# PIC_Schematic.net
KiCad netlist of a schematic drawn in Altium Designer
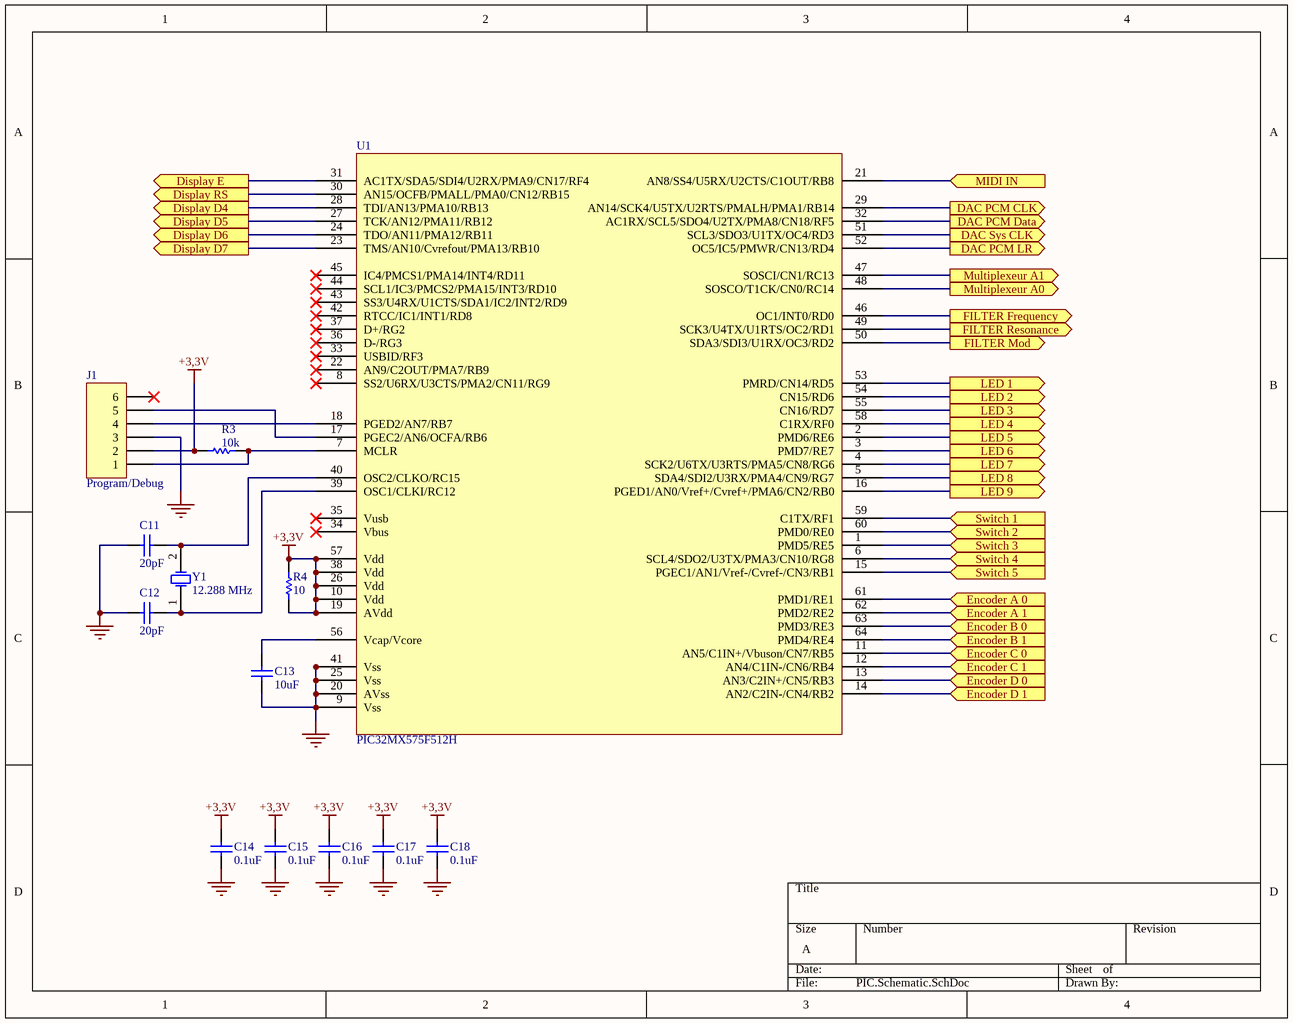
[diagram p0: PIC.Schematic.SchDoc]

(export (version "E")
  (design (tool "Eeschema 10.0.6"))
  (components
    (comp (ref "C11")
      (value "20pF")
      (footprint "CAPC1608N")
      (description "Capacitor (Semiconductor SIM Model)")
      (fields (field (name "PUBLISHER") "Altium Limited"))
      (libsource (lib "Miscellaneous Devices") (part "Cap Semi"))
    )
    (comp (ref "C12")
      (value "20pF")
      (footprint "CAPC1608N")
      (description "Capacitor (Semiconductor SIM Model)")
      (fields (field (name "PUBLISHER") "Altium Limited"))
      (libsource (lib "Miscellaneous Devices") (part "Cap Semi"))
    )
    (comp (ref "C13")
      (value "10uF")
      (footprint "CAPC1608N")
      (description "Capacitor")
      (fields (field (name "PUBLISHER") "Altium Limited"))
      (libsource (lib "Miscellaneous Devices") (part "Cap"))
    )
    (comp (ref "C14")
      (value "0.1uF")
      (footprint "CAPC1608N")
      (description "Capacitor (Semiconductor SIM Model)")
      (fields (field (name "PUBLISHER") "Altium Limited"))
      (libsource (lib "Miscellaneous Devices") (part "Cap Semi"))
    )
    (comp (ref "C15")
      (value "0.1uF")
      (footprint "CAPC1608N")
      (description "Capacitor (Semiconductor SIM Model)")
      (fields (field (name "PUBLISHER") "Altium Limited"))
      (libsource (lib "Miscellaneous Devices") (part "Cap Semi"))
    )
    (comp (ref "C16")
      (value "0.1uF")
      (footprint "CAPC1608N")
      (description "Capacitor (Semiconductor SIM Model)")
      (fields (field (name "PUBLISHER") "Altium Limited"))
      (libsource (lib "Miscellaneous Devices") (part "Cap Semi"))
    )
    (comp (ref "C17")
      (value "0.1uF")
      (footprint "CAPC1608N")
      (description "Capacitor (Semiconductor SIM Model)")
      (fields (field (name "PUBLISHER") "Altium Limited"))
      (libsource (lib "Miscellaneous Devices") (part "Cap Semi"))
    )
    (comp (ref "C18")
      (value "0.1uF")
      (footprint "CAPC1608N")
      (description "Capacitor (Semiconductor SIM Model)")
      (fields (field (name "PUBLISHER") "Altium Limited"))
      (libsource (lib "Miscellaneous Devices") (part "Cap Semi"))
    )
    (comp (ref "J1")
      (value "Program/Debug")
      (footprint "RJ11")
      (description "Header, 6-Pin, Right Angle")
      (fields (field (name "PUBLISHER") "Altium Limited"))
      (libsource (lib "Miscellaneous Connectors") (part "Header 6H"))
    )
    (comp (ref "R3")
      (value "10k")
      (footprint "CAPC1608N")
      (description "Resistor")
      (fields (field (name "PUBLISHER") "Altium Limited"))
      (libsource (lib "Miscellaneous Devices") (part "Res1"))
    )
    (comp (ref "R4")
      (value "10")
      (footprint "CAPC1608N")
      (description "Resistor")
      (fields (field (name "PUBLISHER") "Altium Limited"))
      (libsource (lib "Miscellaneous Devices") (part "Res1"))
    )
    (comp (ref "U1")
      (value "PIC32MX575F512H")
      (footprint "PIC32")
      (libsource (lib "SynthyTwo.Components") (part "PIC32 MX575F512H"))
    )
    (comp (ref "Y1")
      (value "12.288 MHz")
      (footprint "Xtal")
      (description "Crystal Oscillator")
      (fields (field (name "PUBLISHER") "Altium Limited"))
      (libsource (lib "Miscellaneous Devices") (part "XTAL"))
    )
  )
  (nets
    (net (code "1") (name "+3,3V") (class "Default")
      (node (ref "C14") (pin "2") (pinfunction "2_2") (pintype "passive"))
      (node (ref "C15") (pin "2") (pinfunction "2_2") (pintype "passive"))
      (node (ref "C16") (pin "2") (pinfunction "2_2") (pintype "passive"))
      (node (ref "C17") (pin "2") (pinfunction "2_2") (pintype "passive"))
      (node (ref "C18") (pin "2") (pinfunction "2_2") (pintype "passive"))
      (node (ref "J1") (pin "2") (pinfunction "2_2") (pintype "passive"))
      (node (ref "R3") (pin "2") (pinfunction "2_2") (pintype "passive"))
      (node (ref "R4") (pin "1") (pinfunction "1_1") (pintype "passive"))
      (node (ref "R4") (pin "2") (pinfunction "2_2") (pintype "passive"))
      (node (ref "U1") (pin "10") (pinfunction "Vdd_10") (pintype "passive"))
      (node (ref "U1") (pin "19") (pinfunction "AVdd_19") (pintype "passive"))
      (node (ref "U1") (pin "26") (pinfunction "Vdd_26") (pintype "passive"))
      (node (ref "U1") (pin "38") (pinfunction "Vdd_38") (pintype "passive"))
      (node (ref "U1") (pin "57") (pinfunction "Vdd_57") (pintype "passive"))
    )
    (net (code "2") (name "/DAC PCM CLK") (class "Default")
      (node (ref "U1") (pin "29") (pinfunction "AN14/SCK4/U5TX/U2RTS/PMALH/PMA1/RB14_29") (pintype "passive"))
    )
    (net (code "3") (name "/DAC PCM Data") (class "Default")
      (node (ref "U1") (pin "32") (pinfunction "AC1RX/SCL5/SDO4/U2TX/PMA8/CN18/RF5_32") (pintype "passive"))
    )
    (net (code "4") (name "/DAC PCM LR") (class "Default")
      (node (ref "U1") (pin "52") (pinfunction "OC5/IC5/PMWR/CN13/RD4_52") (pintype "passive"))
    )
    (net (code "5") (name "/DAC Sys CLK") (class "Default")
      (node (ref "U1") (pin "51") (pinfunction "SCL3/SDO3/U1TX/OC4/RD3_51") (pintype "passive"))
    )
    (net (code "6") (name "/Display D4") (class "Default")
      (node (ref "U1") (pin "28") (pinfunction "TDI/AN13/PMA10/RB13_28") (pintype "passive"))
    )
    (net (code "7") (name "/Display D5") (class "Default")
      (node (ref "U1") (pin "27") (pinfunction "TCK/AN12/PMA11/RB12_27") (pintype "passive"))
    )
    (net (code "8") (name "/Display D6") (class "Default")
      (node (ref "U1") (pin "24") (pinfunction "TDO/AN11/PMA12/RB11_24") (pintype "passive"))
    )
    (net (code "9") (name "/Display D7") (class "Default")
      (node (ref "U1") (pin "23") (pinfunction "TMS/AN10/Cvrefout/PMA13/RB10_23") (pintype "passive"))
    )
    (net (code "10") (name "/Display E") (class "Default")
      (node (ref "U1") (pin "31") (pinfunction "AC1TX/SDA5/SDI4/U2RX/PMA9/CN17/RF4_31") (pintype "passive"))
    )
    (net (code "11") (name "/Display RS") (class "Default")
      (node (ref "U1") (pin "30") (pinfunction "AN15/OCFB/PMALL/PMA0/CN12/RB15_30") (pintype "passive"))
    )
    (net (code "12") (name "/Encoder A 0") (class "Default")
      (node (ref "U1") (pin "61") (pinfunction "PMD1/RE1_61") (pintype "passive"))
    )
    (net (code "13") (name "/Encoder A 1") (class "Default")
      (node (ref "U1") (pin "62") (pinfunction "PMD2/RE2_62") (pintype "passive"))
    )
    (net (code "14") (name "/Encoder B 0") (class "Default")
      (node (ref "U1") (pin "63") (pinfunction "PMD3/RE3_63") (pintype "passive"))
    )
    (net (code "15") (name "/Encoder B 1") (class "Default")
      (node (ref "U1") (pin "64") (pinfunction "PMD4/RE4_64") (pintype "passive"))
    )
    (net (code "16") (name "/Encoder C 0") (class "Default")
      (node (ref "U1") (pin "11") (pinfunction "AN5/C1IN+/Vbuson/CN7/RB5_11") (pintype "passive"))
    )
    (net (code "17") (name "/Encoder C 1") (class "Default")
      (node (ref "U1") (pin "12") (pinfunction "AN4/C1IN-/CN6/RB4_12") (pintype "passive"))
    )
    (net (code "18") (name "/Encoder D 0") (class "Default")
      (node (ref "U1") (pin "13") (pinfunction "AN3/C2IN+/CN5/RB3_13") (pintype "passive"))
    )
    (net (code "19") (name "/Encoder D 1") (class "Default")
      (node (ref "U1") (pin "14") (pinfunction "AN2/C2IN-/CN4/RB2_14") (pintype "passive"))
    )
    (net (code "20") (name "/FILTER Frequency") (class "Default")
      (node (ref "U1") (pin "46") (pinfunction "OC1/INT0/RD0_46") (pintype "passive"))
    )
    (net (code "21") (name "/FILTER Mod") (class "Default")
      (node (ref "U1") (pin "50") (pinfunction "SDA3/SDI3/U1RX/OC3/RD2_50") (pintype "passive"))
    )
    (net (code "22") (name "/FILTER Resonance") (class "Default")
      (node (ref "U1") (pin "49") (pinfunction "SCK3/U4TX/U1RTS/OC2/RD1_49") (pintype "passive"))
    )
    (net (code "23") (name "/LED 1") (class "Default")
      (node (ref "U1") (pin "53") (pinfunction "PMRD/CN14/RD5_53") (pintype "passive"))
    )
    (net (code "24") (name "/LED 2") (class "Default")
      (node (ref "U1") (pin "54") (pinfunction "CN15/RD6_54") (pintype "passive"))
    )
    (net (code "25") (name "/LED 3") (class "Default")
      (node (ref "U1") (pin "55") (pinfunction "CN16/RD7_55") (pintype "passive"))
    )
    (net (code "26") (name "/LED 4") (class "Default")
      (node (ref "U1") (pin "58") (pinfunction "C1RX/RF0_58") (pintype "passive"))
    )
    (net (code "27") (name "/LED 5") (class "Default")
      (node (ref "U1") (pin "2") (pinfunction "PMD6/RE6_2") (pintype "passive"))
    )
    (net (code "28") (name "/LED 6") (class "Default")
      (node (ref "U1") (pin "3") (pinfunction "PMD7/RE7_3") (pintype "passive"))
    )
    (net (code "29") (name "/LED 7") (class "Default")
      (node (ref "U1") (pin "4") (pinfunction "SCK2/U6TX/U3RTS/PMA5/CN8/RG6_4") (pintype "passive"))
    )
    (net (code "30") (name "/LED 8") (class "Default")
      (node (ref "U1") (pin "5") (pinfunction "SDA4/SDI2/U3RX/PMA4/CN9/RG7_5") (pintype "passive"))
    )
    (net (code "31") (name "/LED 9") (class "Default")
      (node (ref "U1") (pin "16") (pinfunction "PGED1/AN0/Vref+/Cvref+/PMA6/CN2/RB0_16") (pintype "passive"))
    )
    (net (code "32") (name "/MIDI IN") (class "Default")
      (node (ref "U1") (pin "21") (pinfunction "AN8/SS4/U5RX/U2CTS/C1OUT/RB8_21") (pintype "passive"))
    )
    (net (code "33") (name "/Multiplexeur A0") (class "Default")
      (node (ref "U1") (pin "48") (pinfunction "SOSCO/T1CK/CN0/RC14_48") (pintype "passive"))
    )
    (net (code "34") (name "/Multiplexeur A1") (class "Default")
      (node (ref "U1") (pin "47") (pinfunction "SOSCI/CN1/RC13_47") (pintype "passive"))
    )
    (net (code "35") (name "/Switch 1") (class "Default")
      (node (ref "U1") (pin "59") (pinfunction "C1TX/RF1_59") (pintype "passive"))
    )
    (net (code "36") (name "/Switch 2") (class "Default")
      (node (ref "U1") (pin "60") (pinfunction "PMD0/RE0_60") (pintype "passive"))
    )
    (net (code "37") (name "/Switch 3") (class "Default")
      (node (ref "U1") (pin "1") (pinfunction "PMD5/RE5_1") (pintype "passive"))
    )
    (net (code "38") (name "/Switch 4") (class "Default")
      (node (ref "U1") (pin "6") (pinfunction "SCL4/SDO2/U3TX/PMA3/CN10/RG8_6") (pintype "passive"))
    )
    (net (code "39") (name "/Switch 5") (class "Default")
      (node (ref "U1") (pin "15") (pinfunction "PGEC1/AN1/Vref-/Cvref-/CN3/RB1_15") (pintype "passive"))
    )
    (net (code "40") (name "GND") (class "Default")
      (node (ref "C11") (pin "1") (pinfunction "1_1") (pintype "passive"))
      (node (ref "C12") (pin "1") (pinfunction "1_1") (pintype "passive"))
      (node (ref "C13") (pin "1") (pinfunction "1_1") (pintype "passive"))
      (node (ref "C14") (pin "1") (pinfunction "1_1") (pintype "passive"))
      (node (ref "C15") (pin "1") (pinfunction "1_1") (pintype "passive"))
      (node (ref "C16") (pin "1") (pinfunction "1_1") (pintype "passive"))
      (node (ref "C17") (pin "1") (pinfunction "1_1") (pintype "passive"))
      (node (ref "C18") (pin "1") (pinfunction "1_1") (pintype "passive"))
      (node (ref "J1") (pin "3") (pinfunction "3_3") (pintype "passive"))
      (node (ref "U1") (pin "20") (pinfunction "AVss_20") (pintype "passive"))
      (node (ref "U1") (pin "25") (pinfunction "Vss_25") (pintype "passive"))
      (node (ref "U1") (pin "41") (pinfunction "Vss_41") (pintype "passive"))
      (node (ref "U1") (pin "9") (pinfunction "Vss_9") (pintype "passive"))
    )
    (net (code "41") (name "Net-(U1-MCLR)") (class "Default")
      (node (ref "J1") (pin "1") (pinfunction "1_1") (pintype "passive"))
      (node (ref "R3") (pin "1") (pinfunction "1_1") (pintype "passive"))
      (node (ref "U1") (pin "7") (pinfunction "MCLR_7") (pintype "passive"))
    )
    (net (code "42") (name "Net-(U1-OSC1{slash}CLKI{slash}RC12)") (class "Default")
      (node (ref "C12") (pin "2") (pinfunction "2_2") (pintype "passive"))
      (node (ref "U1") (pin "39") (pinfunction "OSC1/CLKI/RC12_39") (pintype "passive"))
      (node (ref "Y1") (pin "1") (pinfunction "OSC1_1") (pintype "passive"))
    )
    (net (code "43") (name "Net-(U1-OSC2{slash}CLKO{slash}RC15)") (class "Default")
      (node (ref "C11") (pin "2") (pinfunction "2_2") (pintype "passive"))
      (node (ref "U1") (pin "40") (pinfunction "OSC2/CLKO/RC15_40") (pintype "passive"))
      (node (ref "Y1") (pin "2") (pinfunction "OSC2_2") (pintype "passive"))
    )
    (net (code "44") (name "Net-(U1-PGEC2{slash}AN6{slash}OCFA{slash}RB6)") (class "Default")
      (node (ref "J1") (pin "5") (pinfunction "5_5") (pintype "passive"))
      (node (ref "U1") (pin "17") (pinfunction "PGEC2/AN6/OCFA/RB6_17") (pintype "passive"))
    )
    (net (code "45") (name "Net-(U1-PGED2{slash}AN7{slash}RB7)") (class "Default")
      (node (ref "J1") (pin "4") (pinfunction "4_4") (pintype "passive"))
      (node (ref "U1") (pin "18") (pinfunction "PGED2/AN7/RB7_18") (pintype "passive"))
    )
    (net (code "46") (name "Net-(U1-Vcap{slash}Vcore)") (class "Default")
      (node (ref "C13") (pin "2") (pinfunction "2_2") (pintype "passive"))
      (node (ref "U1") (pin "56") (pinfunction "Vcap/Vcore_56") (pintype "passive"))
    )
    (net (code "47") (name "unconnected-(J1-Pad6)") (class "Default")
      (node (ref "J1") (pin "6") (pinfunction "6_6") (pintype "passive+no_connect"))
    )
    (net (code "48") (name "unconnected-(U1-AN9{slash}C2OUT{slash}PMA7{slash}RB9-Pad22)") (class "Default")
      (node (ref "U1") (pin "22") (pinfunction "AN9/C2OUT/PMA7/RB9_22") (pintype "passive+no_connect"))
    )
    (net (code "49") (name "unconnected-(U1-D+{slash}RG2-Pad37)") (class "Default")
      (node (ref "U1") (pin "37") (pinfunction "D+/RG2_37") (pintype "passive+no_connect"))
    )
    (net (code "50") (name "unconnected-(U1-D-{slash}RG3-Pad36)") (class "Default")
      (node (ref "U1") (pin "36") (pinfunction "D-/RG3_36") (pintype "passive+no_connect"))
    )
    (net (code "51") (name "unconnected-(U1-IC4{slash}PMCS1{slash}PMA14{slash}INT4{slash}RD11-Pad45)") (class "Default")
      (node (ref "U1") (pin "45") (pinfunction "IC4/PMCS1/PMA14/INT4/RD11_45") (pintype "passive+no_connect"))
    )
    (net (code "52") (name "unconnected-(U1-RTCC{slash}IC1{slash}INT1{slash}RD8-Pad42)") (class "Default")
      (node (ref "U1") (pin "42") (pinfunction "RTCC/IC1/INT1/RD8_42") (pintype "passive+no_connect"))
    )
    (net (code "53") (name "unconnected-(U1-SCL1{slash}IC3{slash}PMCS2{slash}PMA15{slash}INT3{slash}RD10-Pad44)") (class "Default")
      (node (ref "U1") (pin "44") (pinfunction "SCL1/IC3/PMCS2/PMA15/INT3/RD10_44") (pintype "passive+no_connect"))
    )
    (net (code "54") (name "unconnected-(U1-SS2{slash}U6RX{slash}U3CTS{slash}PMA2{slash}CN11{slash}RG9-Pad8)") (class "Default")
      (node (ref "U1") (pin "8") (pinfunction "SS2/U6RX/U3CTS/PMA2/CN11/RG9_8") (pintype "passive+no_connect"))
    )
    (net (code "55") (name "unconnected-(U1-SS3{slash}U4RX{slash}U1CTS{slash}SDA1{slash}IC2{slash}INT2{slash}RD9-Pad43)") (class "Default")
      (node (ref "U1") (pin "43") (pinfunction "SS3/U4RX/U1CTS/SDA1/IC2/INT2/RD9_43") (pintype "passive+no_connect"))
    )
    (net (code "56") (name "unconnected-(U1-USBID{slash}RF3-Pad33)") (class "Default")
      (node (ref "U1") (pin "33") (pinfunction "USBID/RF3_33") (pintype "passive+no_connect"))
    )
    (net (code "57") (name "unconnected-(U1-Vbus-Pad34)") (class "Default")
      (node (ref "U1") (pin "34") (pinfunction "Vbus_34") (pintype "passive+no_connect"))
    )
    (net (code "58") (name "unconnected-(U1-Vusb-Pad35)") (class "Default")
      (node (ref "U1") (pin "35") (pinfunction "Vusb_35") (pintype "passive+no_connect"))
    )
  )
)
